# EnsembleFour.net
KiCad netlist of a schematic drawn in EAGLE
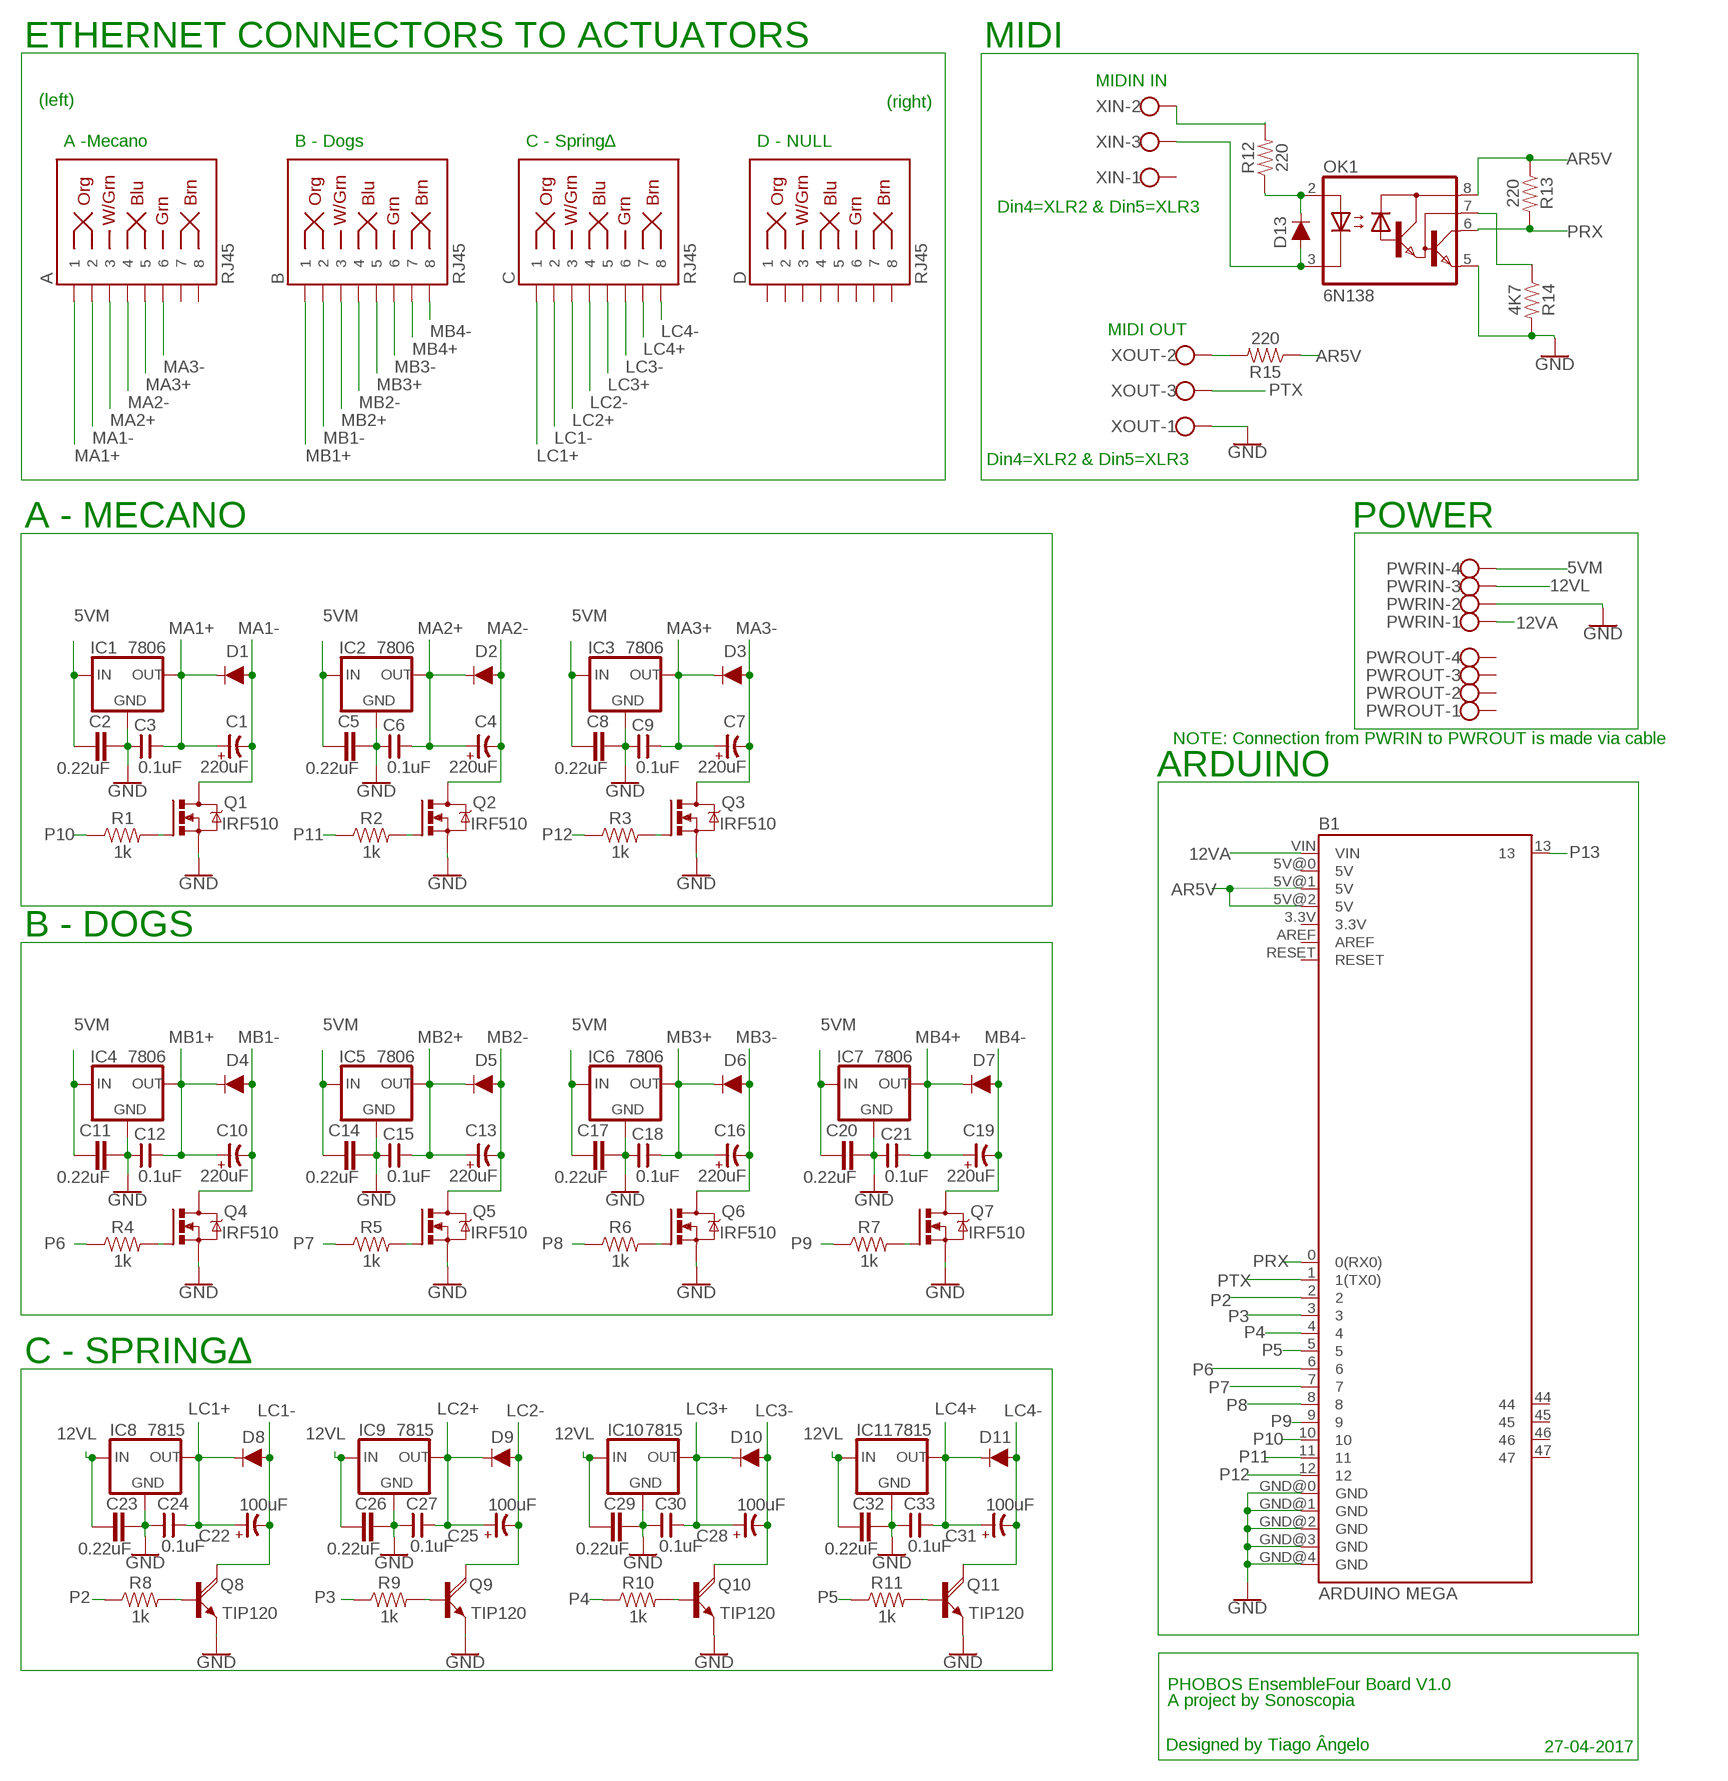
[diagram p0: schematic, sheet 1]

(export (version "E")
  (design (tool "Eeschema 10.0.6"))
  (components
    (comp (ref "A")
      (value "RJ45")
      (footprint "eagle-import:RJ45-8")
      (libsource (lib "eagle-import") (part "RJ45-8"))
    )
    (comp (ref "B")
      (value "RJ45")
      (footprint "eagle-import:RJ45-8")
      (libsource (lib "eagle-import") (part "RJ45-8"))
    )
    (comp (ref "B1")
      (value "ARDUINO MEGA")
      (footprint "eagle-import:ARDUINO_MEGA")
      (libsource (lib "eagle-import") (part "ARDUINO_MEGA_R3FULL"))
    )
    (comp (ref "C")
      (value "RJ45")
      (footprint "eagle-import:RJ45-8")
      (libsource (lib "eagle-import") (part "RJ45-8"))
    )
    (comp (ref "C1")
      (value "220uF")
      (footprint "eagle-import:E-035X080")
      (libsource (lib "eagle-import") (part "CP-E-035X080"))
    )
    (comp (ref "C2")
      (value "0.22uF")
      (footprint "eagle-import:C5B3")
      (libsource (lib "eagle-import") (part "C5/3"))
    )
    (comp (ref "C3")
      (value "0.1uF")
      (footprint "eagle-import:C025-050X025")
      (libsource (lib "eagle-import") (part "CNP-C025-050X025"))
    )
    (comp (ref "C4")
      (value "220uF")
      (footprint "eagle-import:E-035X080")
      (libsource (lib "eagle-import") (part "CP-E-035X080"))
    )
    (comp (ref "C5")
      (value "0.22uF")
      (footprint "eagle-import:C5B3")
      (libsource (lib "eagle-import") (part "C5/3"))
    )
    (comp (ref "C6")
      (value "0.1uF")
      (footprint "eagle-import:C025-050X025")
      (libsource (lib "eagle-import") (part "CNP-C025-050X025"))
    )
    (comp (ref "C7")
      (value "220uF")
      (footprint "eagle-import:E-035X080")
      (libsource (lib "eagle-import") (part "CP-E-035X080"))
    )
    (comp (ref "C8")
      (value "0.22uF")
      (footprint "eagle-import:C5B3")
      (libsource (lib "eagle-import") (part "C5/3"))
    )
    (comp (ref "C9")
      (value "0.1uF")
      (footprint "eagle-import:C025-050X025")
      (libsource (lib "eagle-import") (part "CNP-C025-050X025"))
    )
    (comp (ref "C10")
      (value "220uF")
      (footprint "eagle-import:E-035X080")
      (libsource (lib "eagle-import") (part "CP-E-035X080"))
    )
    (comp (ref "C11")
      (value "0.22uF")
      (footprint "eagle-import:C5B3")
      (libsource (lib "eagle-import") (part "C5/3"))
    )
    (comp (ref "C12")
      (value "0.1uF")
      (footprint "eagle-import:C025-050X025")
      (libsource (lib "eagle-import") (part "CNP-C025-050X025"))
    )
    (comp (ref "C13")
      (value "220uF")
      (footprint "eagle-import:E-035X080")
      (libsource (lib "eagle-import") (part "CP-E-035X080"))
    )
    (comp (ref "C14")
      (value "0.22uF")
      (footprint "eagle-import:C5B3")
      (libsource (lib "eagle-import") (part "C5/3"))
    )
    (comp (ref "C15")
      (value "0.1uF")
      (footprint "eagle-import:C025-050X025")
      (libsource (lib "eagle-import") (part "CNP-C025-050X025"))
    )
    (comp (ref "C16")
      (value "220uF")
      (footprint "eagle-import:E-035X080")
      (libsource (lib "eagle-import") (part "CP-E-035X080"))
    )
    (comp (ref "C17")
      (value "0.22uF")
      (footprint "eagle-import:C5B3")
      (libsource (lib "eagle-import") (part "C5/3"))
    )
    (comp (ref "C18")
      (value "0.1uF")
      (footprint "eagle-import:C025-050X025")
      (libsource (lib "eagle-import") (part "CNP-C025-050X025"))
    )
    (comp (ref "C19")
      (value "220uF")
      (footprint "eagle-import:E-035X080")
      (libsource (lib "eagle-import") (part "CP-E-035X080"))
    )
    (comp (ref "C20")
      (value "0.22uF")
      (footprint "eagle-import:C5B3")
      (libsource (lib "eagle-import") (part "C5/3"))
    )
    (comp (ref "C21")
      (value "0.1uF")
      (footprint "eagle-import:C025-050X025")
      (libsource (lib "eagle-import") (part "CNP-C025-050X025"))
    )
    (comp (ref "C22")
      (value "100uF")
      (footprint "eagle-import:E-020X050")
      (libsource (lib "eagle-import") (part "CP-E-020X050"))
    )
    (comp (ref "C23")
      (value "0.22uF")
      (footprint "eagle-import:C5B3")
      (libsource (lib "eagle-import") (part "C5/3"))
    )
    (comp (ref "C24")
      (value "0.1uF")
      (footprint "eagle-import:C025-050X025")
      (libsource (lib "eagle-import") (part "CNP-C025-050X025"))
    )
    (comp (ref "C25")
      (value "100uF")
      (footprint "eagle-import:E-020X050")
      (libsource (lib "eagle-import") (part "CP-E-020X050"))
    )
    (comp (ref "C26")
      (value "0.22uF")
      (footprint "eagle-import:C5B3")
      (libsource (lib "eagle-import") (part "C5/3"))
    )
    (comp (ref "C27")
      (value "0.1uF")
      (footprint "eagle-import:C025-050X025")
      (libsource (lib "eagle-import") (part "CNP-C025-050X025"))
    )
    (comp (ref "C28")
      (value "100uF")
      (footprint "eagle-import:E-020X050")
      (libsource (lib "eagle-import") (part "CP-E-020X050"))
    )
    (comp (ref "C29")
      (value "0.22uF")
      (footprint "eagle-import:C5B3")
      (libsource (lib "eagle-import") (part "C5/3"))
    )
    (comp (ref "C30")
      (value "0.1uF")
      (footprint "eagle-import:C025-050X025")
      (libsource (lib "eagle-import") (part "CNP-C025-050X025"))
    )
    (comp (ref "C31")
      (value "100uF")
      (footprint "eagle-import:E-020X050")
      (libsource (lib "eagle-import") (part "CP-E-020X050"))
    )
    (comp (ref "C32")
      (value "0.22uF")
      (footprint "eagle-import:C5B3")
      (libsource (lib "eagle-import") (part "C5/3"))
    )
    (comp (ref "C33")
      (value "0.1uF")
      (footprint "eagle-import:C025-050X025")
      (libsource (lib "eagle-import") (part "CNP-C025-050X025"))
    )
    (comp (ref "D")
      (value "RJ45")
      (footprint "eagle-import:RJ45-8")
      (libsource (lib "eagle-import") (part "RJ45-8"))
    )
    (comp (ref "D1")
      (value "1A/50V/1.1V")
      (footprint "eagle-import:DIODE-1N4001-KIT")
      (libsource (lib "eagle-import") (part "DIODE-KIT2"))
    )
    (comp (ref "D2")
      (value "1A/50V/1.1V")
      (footprint "eagle-import:DIODE-1N4001-KIT")
      (libsource (lib "eagle-import") (part "DIODE-KIT2"))
    )
    (comp (ref "D3")
      (value "1A/50V/1.1V")
      (footprint "eagle-import:DIODE-1N4001-KIT")
      (libsource (lib "eagle-import") (part "DIODE-KIT2"))
    )
    (comp (ref "D4")
      (value "1A/50V/1.1V")
      (footprint "eagle-import:DIODE-1N4001-KIT")
      (libsource (lib "eagle-import") (part "DIODE-KIT2"))
    )
    (comp (ref "D5")
      (value "1A/50V/1.1V")
      (footprint "eagle-import:DIODE-1N4001-KIT")
      (libsource (lib "eagle-import") (part "DIODE-KIT2"))
    )
    (comp (ref "D6")
      (value "1A/50V/1.1V")
      (footprint "eagle-import:DIODE-1N4001-KIT")
      (libsource (lib "eagle-import") (part "DIODE-KIT2"))
    )
    (comp (ref "D7")
      (value "1A/50V/1.1V")
      (footprint "eagle-import:DIODE-1N4001-KIT")
      (libsource (lib "eagle-import") (part "DIODE-KIT2"))
    )
    (comp (ref "D8")
      (value "1A/50V/1.1V")
      (footprint "eagle-import:DIODE-1N4001-KIT")
      (libsource (lib "eagle-import") (part "DIODE-KIT2"))
    )
    (comp (ref "D9")
      (value "1A/50V/1.1V")
      (footprint "eagle-import:DIODE-1N4001-KIT")
      (libsource (lib "eagle-import") (part "DIODE-KIT2"))
    )
    (comp (ref "D10")
      (value "1A/50V/1.1V")
      (footprint "eagle-import:DIODE-1N4001-KIT")
      (libsource (lib "eagle-import") (part "DIODE-KIT2"))
    )
    (comp (ref "D11")
      (value "1A/50V/1.1V")
      (footprint "eagle-import:DIODE-1N4001-KIT")
      (libsource (lib "eagle-import") (part "DIODE-KIT2"))
    )
    (comp (ref "D13")
      (value "200mA/100V/1V")
      (footprint "eagle-import:DIODE-1N4148")
      (libsource (lib "eagle-import") (part "DIODE-1N4148"))
    )
    (comp (ref "IC1")
      (value "7806")
      (footprint "eagle-import:78XXS")
      (libsource (lib "eagle-import") (part "78XXS"))
    )
    (comp (ref "IC2")
      (value "7806")
      (footprint "eagle-import:78XXS")
      (libsource (lib "eagle-import") (part "78XXS"))
    )
    (comp (ref "IC3")
      (value "7806")
      (footprint "eagle-import:78XXS")
      (libsource (lib "eagle-import") (part "78XXS"))
    )
    (comp (ref "IC4")
      (value "7806")
      (footprint "eagle-import:78XXS")
      (libsource (lib "eagle-import") (part "78XXS"))
    )
    (comp (ref "IC5")
      (value "7806")
      (footprint "eagle-import:78XXS")
      (libsource (lib "eagle-import") (part "78XXS"))
    )
    (comp (ref "IC6")
      (value "7806")
      (footprint "eagle-import:78XXS")
      (libsource (lib "eagle-import") (part "78XXS"))
    )
    (comp (ref "IC7")
      (value "7806")
      (footprint "eagle-import:78XXS")
      (libsource (lib "eagle-import") (part "78XXS"))
    )
    (comp (ref "IC8")
      (value "7815")
      (footprint "eagle-import:78XXS")
      (libsource (lib "eagle-import") (part "78XXS"))
    )
    (comp (ref "IC9")
      (value "7815")
      (footprint "eagle-import:78XXS")
      (libsource (lib "eagle-import") (part "78XXS"))
    )
    (comp (ref "IC10")
      (value "7815")
      (footprint "eagle-import:78XXS")
      (libsource (lib "eagle-import") (part "78XXS"))
    )
    (comp (ref "IC11")
      (value "7815")
      (footprint "eagle-import:78XXS")
      (libsource (lib "eagle-import") (part "78XXS"))
    )
    (comp (ref "OK1")
      (value "6N138")
      (footprint "eagle-import:DIL08")
      (fields (field (name "MF") "VISHAY/TELEFUNKEN"))
      (libsource (lib "eagle-import") (part "6N138"))
    )
    (comp (ref "PWRIN")
      (value "W237-4")
      (footprint "eagle-import:W237-4")
      (libsource (lib "eagle-import") (part "W237-4"))
    )
    (comp (ref "PWROUT")
      (value "W237-4")
      (footprint "eagle-import:W237-4")
      (libsource (lib "eagle-import") (part "W237-4"))
    )
    (comp (ref "Q1")
      (value "IRF510")
      (footprint "eagle-import:TO220BV")
      (libsource (lib "eagle-import") (part "IRF520"))
    )
    (comp (ref "Q2")
      (value "IRF510")
      (footprint "eagle-import:TO220BV")
      (libsource (lib "eagle-import") (part "IRF520"))
    )
    (comp (ref "Q3")
      (value "IRF510")
      (footprint "eagle-import:TO220BV")
      (libsource (lib "eagle-import") (part "IRF520"))
    )
    (comp (ref "Q4")
      (value "IRF510")
      (footprint "eagle-import:TO220BV")
      (libsource (lib "eagle-import") (part "IRF520"))
    )
    (comp (ref "Q5")
      (value "IRF510")
      (footprint "eagle-import:TO220BV")
      (libsource (lib "eagle-import") (part "IRF520"))
    )
    (comp (ref "Q6")
      (value "IRF510")
      (footprint "eagle-import:TO220BV")
      (libsource (lib "eagle-import") (part "IRF520"))
    )
    (comp (ref "Q7")
      (value "IRF510")
      (footprint "eagle-import:TO220BV")
      (libsource (lib "eagle-import") (part "IRF520"))
    )
    (comp (ref "Q8")
      (value "TIP120")
      (footprint "eagle-import:TO220AV")
      (libsource (lib "eagle-import") (part "TIP120V"))
    )
    (comp (ref "Q9")
      (value "TIP120")
      (footprint "eagle-import:TO220AV")
      (libsource (lib "eagle-import") (part "TIP120V"))
    )
    (comp (ref "Q10")
      (value "TIP120")
      (footprint "eagle-import:TO220AV")
      (libsource (lib "eagle-import") (part "TIP120V"))
    )
    (comp (ref "Q11")
      (value "TIP120")
      (footprint "eagle-import:TO220AV")
      (libsource (lib "eagle-import") (part "TIP120V"))
    )
    (comp (ref "R1")
      (value "1k")
      (footprint "eagle-import:AXIAL-0.1")
      (libsource (lib "eagle-import") (part "1KOHM-VERT-1/4W-1%"))
    )
    (comp (ref "R2")
      (value "1k")
      (footprint "eagle-import:AXIAL-0.1")
      (libsource (lib "eagle-import") (part "1KOHM-VERT-1/4W-1%"))
    )
    (comp (ref "R3")
      (value "1k")
      (footprint "eagle-import:AXIAL-0.1")
      (libsource (lib "eagle-import") (part "1KOHM-VERT-1/4W-1%"))
    )
    (comp (ref "R4")
      (value "1k")
      (footprint "eagle-import:AXIAL-0.1")
      (libsource (lib "eagle-import") (part "1KOHM-VERT-1/4W-1%"))
    )
    (comp (ref "R5")
      (value "1k")
      (footprint "eagle-import:AXIAL-0.1")
      (libsource (lib "eagle-import") (part "1KOHM-VERT-1/4W-1%"))
    )
    (comp (ref "R6")
      (value "1k")
      (footprint "eagle-import:AXIAL-0.1")
      (libsource (lib "eagle-import") (part "1KOHM-VERT-1/4W-1%"))
    )
    (comp (ref "R7")
      (value "1k")
      (footprint "eagle-import:AXIAL-0.1")
      (libsource (lib "eagle-import") (part "1KOHM-VERT-1/4W-1%"))
    )
    (comp (ref "R8")
      (value "1k")
      (footprint "eagle-import:AXIAL-0.1")
      (libsource (lib "eagle-import") (part "1KOHM-VERT-1/4W-1%"))
    )
    (comp (ref "R9")
      (value "1k")
      (footprint "eagle-import:AXIAL-0.1")
      (libsource (lib "eagle-import") (part "1KOHM-VERT-1/4W-1%"))
    )
    (comp (ref "R10")
      (value "1k")
      (footprint "eagle-import:AXIAL-0.1")
      (libsource (lib "eagle-import") (part "1KOHM-VERT-1/4W-1%"))
    )
    (comp (ref "R11")
      (value "1k")
      (footprint "eagle-import:AXIAL-0.1")
      (libsource (lib "eagle-import") (part "1KOHM-VERT-1/4W-1%"))
    )
    (comp (ref "R12")
      (value "220")
      (footprint "eagle-import:AXIAL-0.3")
      (libsource (lib "eagle-import") (part "1KOHM-HORIZ-1/4W-5%"))
    )
    (comp (ref "R13")
      (value "220")
      (footprint "eagle-import:AXIAL-0.3")
      (libsource (lib "eagle-import") (part "1KOHM-HORIZ-1/4W-5%"))
    )
    (comp (ref "R14")
      (value "4K7")
      (footprint "eagle-import:AXIAL-0.3")
      (libsource (lib "eagle-import") (part "1KOHM-HORIZ-1/4W-5%"))
    )
    (comp (ref "R15")
      (value "220")
      (footprint "eagle-import:AXIAL-0.3")
      (libsource (lib "eagle-import") (part "1KOHM-HORIZ-1/4W-5%"))
    )
    (comp (ref "XIN")
      (value "W237-103")
      (footprint "eagle-import:W237-103")
      (fields (field (name "MPN") "237-103"))
      (libsource (lib "eagle-import") (part "W237-103"))
    )
    (comp (ref "XOUT")
      (value "W237-103")
      (footprint "eagle-import:W237-103")
      (fields (field (name "MPN") "237-103"))
      (libsource (lib "eagle-import") (part "W237-103"))
    )
  )
  (nets
    (net (code "1") (name "/5VM") (class "Default")
      (node (ref "C11") (pin "1") (pinfunction "1_1") (pintype "passive"))
      (node (ref "C14") (pin "1") (pinfunction "1_1") (pintype "passive"))
      (node (ref "C17") (pin "1") (pinfunction "1_1") (pintype "passive"))
      (node (ref "C2") (pin "1") (pinfunction "1_1") (pintype "passive"))
      (node (ref "C20") (pin "1") (pinfunction "1_1") (pintype "passive"))
      (node (ref "C5") (pin "1") (pinfunction "1_1") (pintype "passive"))
      (node (ref "C8") (pin "1") (pinfunction "1_1") (pintype "passive"))
      (node (ref "IC1") (pin "IN") (pinfunction "IN_IN") (pintype "input"))
      (node (ref "IC2") (pin "IN") (pinfunction "IN_IN") (pintype "input"))
      (node (ref "IC3") (pin "IN") (pinfunction "IN_IN") (pintype "input"))
      (node (ref "IC4") (pin "IN") (pinfunction "IN_IN") (pintype "input"))
      (node (ref "IC5") (pin "IN") (pinfunction "IN_IN") (pintype "input"))
      (node (ref "IC6") (pin "IN") (pinfunction "IN_IN") (pintype "input"))
      (node (ref "IC7") (pin "IN") (pinfunction "IN_IN") (pintype "input"))
      (node (ref "PWRIN") (pin "4") (pinfunction "KL_4") (pintype "passive"))
    )
    (net (code "2") (name "/12VA") (class "Default")
      (node (ref "B1") (pin "VIN") (pinfunction "VIN_VIN") (pintype "bidirectional"))
      (node (ref "PWRIN") (pin "1") (pinfunction "KL_1") (pintype "passive"))
    )
    (net (code "3") (name "/12VL") (class "Default")
      (node (ref "C23") (pin "1") (pinfunction "1_1") (pintype "passive"))
      (node (ref "C26") (pin "1") (pinfunction "1_1") (pintype "passive"))
      (node (ref "C29") (pin "1") (pinfunction "1_1") (pintype "passive"))
      (node (ref "C32") (pin "1") (pinfunction "1_1") (pintype "passive"))
      (node (ref "IC10") (pin "IN") (pinfunction "IN_IN") (pintype "input"))
      (node (ref "IC11") (pin "IN") (pinfunction "IN_IN") (pintype "input"))
      (node (ref "IC8") (pin "IN") (pinfunction "IN_IN") (pintype "input"))
      (node (ref "IC9") (pin "IN") (pinfunction "IN_IN") (pintype "input"))
      (node (ref "PWRIN") (pin "3") (pinfunction "KL_3") (pintype "passive"))
    )
    (net (code "4") (name "/AR5V") (class "Default")
      (node (ref "B1") (pin "5V@1") (pinfunction "5V_5V@1") (pintype "bidirectional"))
      (node (ref "B1") (pin "5V@2") (pinfunction "5V_5V@2") (pintype "bidirectional"))
      (node (ref "OK1") (pin "8") (pinfunction "VCC_8") (pintype "passive"))
      (node (ref "R13") (pin "P$1") (pinfunction "1_P$1") (pintype "passive"))
      (node (ref "R15") (pin "P$1") (pinfunction "1_P$1") (pintype "passive"))
    )
    (net (code "5") (name "/LC1+") (class "Default")
      (node (ref "C") (pin "1") (pinfunction "1_1") (pintype "bidirectional"))
      (node (ref "C22") (pin "+") (pinfunction "+_+") (pintype "passive"))
      (node (ref "C24") (pin "2") (pinfunction "2_2") (pintype "passive"))
      (node (ref "D8") (pin "C") (pinfunction "C_C") (pintype "passive"))
      (node (ref "IC8") (pin "OUT") (pinfunction "OUT_OUT") (pintype "passive"))
    )
    (net (code "6") (name "/LC1-") (class "Default")
      (node (ref "C") (pin "2") (pinfunction "2_2") (pintype "bidirectional"))
      (node (ref "C22") (pin "-") (pinfunction "-_-") (pintype "passive"))
      (node (ref "D8") (pin "A") (pinfunction "A_A") (pintype "passive"))
      (node (ref "Q8") (pin "C") (pinfunction "C_C") (pintype "passive"))
    )
    (net (code "7") (name "/LC2+") (class "Default")
      (node (ref "C") (pin "3") (pinfunction "3_3") (pintype "bidirectional"))
      (node (ref "C25") (pin "+") (pinfunction "+_+") (pintype "passive"))
      (node (ref "C27") (pin "2") (pinfunction "2_2") (pintype "passive"))
      (node (ref "D9") (pin "C") (pinfunction "C_C") (pintype "passive"))
      (node (ref "IC9") (pin "OUT") (pinfunction "OUT_OUT") (pintype "passive"))
    )
    (net (code "8") (name "/LC2-") (class "Default")
      (node (ref "C") (pin "4") (pinfunction "4_4") (pintype "bidirectional"))
      (node (ref "C25") (pin "-") (pinfunction "-_-") (pintype "passive"))
      (node (ref "D9") (pin "A") (pinfunction "A_A") (pintype "passive"))
      (node (ref "Q9") (pin "C") (pinfunction "C_C") (pintype "passive"))
    )
    (net (code "9") (name "/LC3+") (class "Default")
      (node (ref "C") (pin "5") (pinfunction "5_5") (pintype "bidirectional"))
      (node (ref "C28") (pin "+") (pinfunction "+_+") (pintype "passive"))
      (node (ref "C30") (pin "2") (pinfunction "2_2") (pintype "passive"))
      (node (ref "D10") (pin "C") (pinfunction "C_C") (pintype "passive"))
      (node (ref "IC10") (pin "OUT") (pinfunction "OUT_OUT") (pintype "passive"))
    )
    (net (code "10") (name "/LC3-") (class "Default")
      (node (ref "C") (pin "6") (pinfunction "6_6") (pintype "bidirectional"))
      (node (ref "C28") (pin "-") (pinfunction "-_-") (pintype "passive"))
      (node (ref "D10") (pin "A") (pinfunction "A_A") (pintype "passive"))
      (node (ref "Q10") (pin "C") (pinfunction "C_C") (pintype "passive"))
    )
    (net (code "11") (name "/LC4+") (class "Default")
      (node (ref "C") (pin "7") (pinfunction "7_7") (pintype "bidirectional"))
      (node (ref "C31") (pin "+") (pinfunction "+_+") (pintype "passive"))
      (node (ref "C33") (pin "2") (pinfunction "2_2") (pintype "passive"))
      (node (ref "D11") (pin "C") (pinfunction "C_C") (pintype "passive"))
      (node (ref "IC11") (pin "OUT") (pinfunction "OUT_OUT") (pintype "passive"))
    )
    (net (code "12") (name "/LC4-") (class "Default")
      (node (ref "C") (pin "8") (pinfunction "8_8") (pintype "bidirectional"))
      (node (ref "C31") (pin "-") (pinfunction "-_-") (pintype "passive"))
      (node (ref "D11") (pin "A") (pinfunction "A_A") (pintype "passive"))
      (node (ref "Q11") (pin "C") (pinfunction "C_C") (pintype "passive"))
    )
    (net (code "13") (name "/MA1+") (class "Default")
      (node (ref "A") (pin "1") (pinfunction "1_1") (pintype "bidirectional"))
      (node (ref "C1") (pin "+") (pinfunction "+_+") (pintype "passive"))
      (node (ref "C3") (pin "2") (pinfunction "2_2") (pintype "passive"))
      (node (ref "D1") (pin "C") (pinfunction "C_C") (pintype "passive"))
      (node (ref "IC1") (pin "OUT") (pinfunction "OUT_OUT") (pintype "passive"))
    )
    (net (code "14") (name "/MA1-") (class "Default")
      (node (ref "A") (pin "2") (pinfunction "2_2") (pintype "bidirectional"))
      (node (ref "C1") (pin "-") (pinfunction "-_-") (pintype "passive"))
      (node (ref "D1") (pin "A") (pinfunction "A_A") (pintype "passive"))
      (node (ref "Q1") (pin "D") (pinfunction "D_D") (pintype "passive"))
    )
    (net (code "15") (name "/MA2+") (class "Default")
      (node (ref "A") (pin "3") (pinfunction "3_3") (pintype "bidirectional"))
      (node (ref "C4") (pin "+") (pinfunction "+_+") (pintype "passive"))
      (node (ref "C6") (pin "2") (pinfunction "2_2") (pintype "passive"))
      (node (ref "D2") (pin "C") (pinfunction "C_C") (pintype "passive"))
      (node (ref "IC2") (pin "OUT") (pinfunction "OUT_OUT") (pintype "passive"))
    )
    (net (code "16") (name "/MA2-") (class "Default")
      (node (ref "A") (pin "4") (pinfunction "4_4") (pintype "bidirectional"))
      (node (ref "C4") (pin "-") (pinfunction "-_-") (pintype "passive"))
      (node (ref "D2") (pin "A") (pinfunction "A_A") (pintype "passive"))
      (node (ref "Q2") (pin "D") (pinfunction "D_D") (pintype "passive"))
    )
    (net (code "17") (name "/MA3+") (class "Default")
      (node (ref "A") (pin "5") (pinfunction "5_5") (pintype "bidirectional"))
      (node (ref "C7") (pin "+") (pinfunction "+_+") (pintype "passive"))
      (node (ref "C9") (pin "2") (pinfunction "2_2") (pintype "passive"))
      (node (ref "D3") (pin "C") (pinfunction "C_C") (pintype "passive"))
      (node (ref "IC3") (pin "OUT") (pinfunction "OUT_OUT") (pintype "passive"))
    )
    (net (code "18") (name "/MA3-") (class "Default")
      (node (ref "A") (pin "6") (pinfunction "6_6") (pintype "bidirectional"))
      (node (ref "C7") (pin "-") (pinfunction "-_-") (pintype "passive"))
      (node (ref "D3") (pin "A") (pinfunction "A_A") (pintype "passive"))
      (node (ref "Q3") (pin "D") (pinfunction "D_D") (pintype "passive"))
    )
    (net (code "19") (name "/MB1+") (class "Default")
      (node (ref "B") (pin "1") (pinfunction "1_1") (pintype "bidirectional"))
      (node (ref "C10") (pin "+") (pinfunction "+_+") (pintype "passive"))
      (node (ref "C12") (pin "2") (pinfunction "2_2") (pintype "passive"))
      (node (ref "D4") (pin "C") (pinfunction "C_C") (pintype "passive"))
      (node (ref "IC4") (pin "OUT") (pinfunction "OUT_OUT") (pintype "passive"))
    )
    (net (code "20") (name "/MB1-") (class "Default")
      (node (ref "B") (pin "2") (pinfunction "2_2") (pintype "bidirectional"))
      (node (ref "C10") (pin "-") (pinfunction "-_-") (pintype "passive"))
      (node (ref "D4") (pin "A") (pinfunction "A_A") (pintype "passive"))
      (node (ref "Q4") (pin "D") (pinfunction "D_D") (pintype "passive"))
    )
    (net (code "21") (name "/MB2+") (class "Default")
      (node (ref "B") (pin "3") (pinfunction "3_3") (pintype "bidirectional"))
      (node (ref "C13") (pin "+") (pinfunction "+_+") (pintype "passive"))
      (node (ref "C15") (pin "2") (pinfunction "2_2") (pintype "passive"))
      (node (ref "D5") (pin "C") (pinfunction "C_C") (pintype "passive"))
      (node (ref "IC5") (pin "OUT") (pinfunction "OUT_OUT") (pintype "passive"))
    )
    (net (code "22") (name "/MB2-") (class "Default")
      (node (ref "B") (pin "4") (pinfunction "4_4") (pintype "bidirectional"))
      (node (ref "C13") (pin "-") (pinfunction "-_-") (pintype "passive"))
      (node (ref "D5") (pin "A") (pinfunction "A_A") (pintype "passive"))
      (node (ref "Q5") (pin "D") (pinfunction "D_D") (pintype "passive"))
    )
    (net (code "23") (name "/MB3+") (class "Default")
      (node (ref "B") (pin "5") (pinfunction "5_5") (pintype "bidirectional"))
      (node (ref "C16") (pin "+") (pinfunction "+_+") (pintype "passive"))
      (node (ref "C18") (pin "2") (pinfunction "2_2") (pintype "passive"))
      (node (ref "D6") (pin "C") (pinfunction "C_C") (pintype "passive"))
      (node (ref "IC6") (pin "OUT") (pinfunction "OUT_OUT") (pintype "passive"))
    )
    (net (code "24") (name "/MB3-") (class "Default")
      (node (ref "B") (pin "6") (pinfunction "6_6") (pintype "bidirectional"))
      (node (ref "C16") (pin "-") (pinfunction "-_-") (pintype "passive"))
      (node (ref "D6") (pin "A") (pinfunction "A_A") (pintype "passive"))
      (node (ref "Q6") (pin "D") (pinfunction "D_D") (pintype "passive"))
    )
    (net (code "25") (name "/MB4+") (class "Default")
      (node (ref "B") (pin "7") (pinfunction "7_7") (pintype "bidirectional"))
      (node (ref "C19") (pin "+") (pinfunction "+_+") (pintype "passive"))
      (node (ref "C21") (pin "2") (pinfunction "2_2") (pintype "passive"))
      (node (ref "D7") (pin "C") (pinfunction "C_C") (pintype "passive"))
      (node (ref "IC7") (pin "OUT") (pinfunction "OUT_OUT") (pintype "passive"))
    )
    (net (code "26") (name "/MB4-") (class "Default")
      (node (ref "B") (pin "8") (pinfunction "8_8") (pintype "bidirectional"))
      (node (ref "C19") (pin "-") (pinfunction "-_-") (pintype "passive"))
      (node (ref "D7") (pin "A") (pinfunction "A_A") (pintype "passive"))
      (node (ref "Q7") (pin "D") (pinfunction "D_D") (pintype "passive"))
    )
    (net (code "27") (name "/P2") (class "Default")
      (node (ref "B1") (pin "2") (pinfunction "2_2") (pintype "bidirectional"))
      (node (ref "R8") (pin "P$1") (pinfunction "1_P$1") (pintype "passive"))
    )
    (net (code "28") (name "/P3") (class "Default")
      (node (ref "B1") (pin "3") (pinfunction "3_3") (pintype "bidirectional"))
      (node (ref "R9") (pin "P$1") (pinfunction "1_P$1") (pintype "passive"))
    )
    (net (code "29") (name "/P4") (class "Default")
      (node (ref "B1") (pin "4") (pinfunction "4_4") (pintype "bidirectional"))
      (node (ref "R10") (pin "P$1") (pinfunction "1_P$1") (pintype "passive"))
    )
    (net (code "30") (name "/P5") (class "Default")
      (node (ref "B1") (pin "5") (pinfunction "5_5") (pintype "bidirectional"))
      (node (ref "R11") (pin "P$1") (pinfunction "1_P$1") (pintype "passive"))
    )
    (net (code "31") (name "/P6") (class "Default")
      (node (ref "B1") (pin "6") (pinfunction "6_6") (pintype "bidirectional"))
      (node (ref "R4") (pin "P$1") (pinfunction "1_P$1") (pintype "passive"))
    )
    (net (code "32") (name "/P7") (class "Default")
      (node (ref "B1") (pin "7") (pinfunction "7_7") (pintype "bidirectional"))
      (node (ref "R5") (pin "P$1") (pinfunction "1_P$1") (pintype "passive"))
    )
    (net (code "33") (name "/P8") (class "Default")
      (node (ref "B1") (pin "8") (pinfunction "8_8") (pintype "bidirectional"))
      (node (ref "R6") (pin "P$1") (pinfunction "1_P$1") (pintype "passive"))
    )
    (net (code "34") (name "/P9") (class "Default")
      (node (ref "B1") (pin "9") (pinfunction "9_9") (pintype "bidirectional"))
      (node (ref "R7") (pin "P$1") (pinfunction "1_P$1") (pintype "passive"))
    )
    (net (code "35") (name "/P10") (class "Default")
      (node (ref "B1") (pin "10") (pinfunction "10_10") (pintype "bidirectional"))
      (node (ref "R1") (pin "P$1") (pinfunction "1_P$1") (pintype "passive"))
    )
    (net (code "36") (name "/P11") (class "Default")
      (node (ref "B1") (pin "11") (pinfunction "11_11") (pintype "bidirectional"))
      (node (ref "R2") (pin "P$1") (pinfunction "1_P$1") (pintype "passive"))
    )
    (net (code "37") (name "/P12") (class "Default")
      (node (ref "B1") (pin "12") (pinfunction "12_12") (pintype "bidirectional"))
      (node (ref "R3") (pin "P$1") (pinfunction "1_P$1") (pintype "passive"))
    )
    (net (code "38") (name "/P13") (class "Default")
      (node (ref "B1") (pin "13") (pinfunction "13_13") (pintype "bidirectional"))
    )
    (net (code "39") (name "/PRX") (class "Default")
      (node (ref "B1") (pin "0") (pinfunction "0(RX0)_0") (pintype "bidirectional"))
      (node (ref "OK1") (pin "6") (pinfunction "VO_6") (pintype "passive"))
      (node (ref "R13") (pin "P$2") (pinfunction "2_P$2") (pintype "passive"))
    )
    (net (code "40") (name "/PTX") (class "Default")
      (node (ref "B1") (pin "1") (pinfunction "1(TX0)_1") (pintype "bidirectional"))
      (node (ref "XOUT") (pin "3") (pinfunction "KL_3") (pintype "passive"))
    )
    (net (code "41") (name "GND") (class "Default")
      (node (ref "B1") (pin "GND@0") (pinfunction "GND_GND@0") (pintype "bidirectional"))
      (node (ref "B1") (pin "GND@1") (pinfunction "GND_GND@1") (pintype "bidirectional"))
      (node (ref "B1") (pin "GND@2") (pinfunction "GND_GND@2") (pintype "bidirectional"))
      (node (ref "B1") (pin "GND@3") (pinfunction "GND_GND@3") (pintype "bidirectional"))
      (node (ref "B1") (pin "GND@4") (pinfunction "GND_GND@4") (pintype "bidirectional"))
      (node (ref "C11") (pin "2") (pinfunction "2_2") (pintype "passive"))
      (node (ref "C12") (pin "1") (pinfunction "1_1") (pintype "passive"))
      (node (ref "C14") (pin "2") (pinfunction "2_2") (pintype "passive"))
      (node (ref "C15") (pin "1") (pinfunction "1_1") (pintype "passive"))
      (node (ref "C17") (pin "2") (pinfunction "2_2") (pintype "passive"))
      (node (ref "C18") (pin "1") (pinfunction "1_1") (pintype "passive"))
      (node (ref "C2") (pin "2") (pinfunction "2_2") (pintype "passive"))
      (node (ref "C20") (pin "2") (pinfunction "2_2") (pintype "passive"))
      (node (ref "C21") (pin "1") (pinfunction "1_1") (pintype "passive"))
      (node (ref "C23") (pin "2") (pinfunction "2_2") (pintype "passive"))
      (node (ref "C24") (pin "1") (pinfunction "1_1") (pintype "passive"))
      (node (ref "C26") (pin "2") (pinfunction "2_2") (pintype "passive"))
      (node (ref "C27") (pin "1") (pinfunction "1_1") (pintype "passive"))
      (node (ref "C29") (pin "2") (pinfunction "2_2") (pintype "passive"))
      (node (ref "C3") (pin "1") (pinfunction "1_1") (pintype "passive"))
      (node (ref "C30") (pin "1") (pinfunction "1_1") (pintype "passive"))
      (node (ref "C32") (pin "2") (pinfunction "2_2") (pintype "passive"))
      (node (ref "C33") (pin "1") (pinfunction "1_1") (pintype "passive"))
      (node (ref "C5") (pin "2") (pinfunction "2_2") (pintype "passive"))
      (node (ref "C6") (pin "1") (pinfunction "1_1") (pintype "passive"))
      (node (ref "C8") (pin "2") (pinfunction "2_2") (pintype "passive"))
      (node (ref "C9") (pin "1") (pinfunction "1_1") (pintype "passive"))
      (node (ref "IC1") (pin "GND") (pinfunction "GND_GND") (pintype "input"))
      (node (ref "IC10") (pin "GND") (pinfunction "GND_GND") (pintype "input"))
      (node (ref "IC11") (pin "GND") (pinfunction "GND_GND") (pintype "input"))
      (node (ref "IC2") (pin "GND") (pinfunction "GND_GND") (pintype "input"))
      (node (ref "IC3") (pin "GND") (pinfunction "GND_GND") (pintype "input"))
      (node (ref "IC4") (pin "GND") (pinfunction "GND_GND") (pintype "input"))
      (node (ref "IC5") (pin "GND") (pinfunction "GND_GND") (pintype "input"))
      (node (ref "IC6") (pin "GND") (pinfunction "GND_GND") (pintype "input"))
      (node (ref "IC7") (pin "GND") (pinfunction "GND_GND") (pintype "input"))
      (node (ref "IC8") (pin "GND") (pinfunction "GND_GND") (pintype "input"))
      (node (ref "IC9") (pin "GND") (pinfunction "GND_GND") (pintype "input"))
      (node (ref "OK1") (pin "5") (pinfunction "GND_5") (pintype "passive"))
      (node (ref "PWRIN") (pin "2") (pinfunction "KL_2") (pintype "passive"))
      (node (ref "Q1") (pin "S") (pinfunction "S_S") (pintype "passive"))
      (node (ref "Q10") (pin "E") (pinfunction "E_E") (pintype "passive"))
      (node (ref "Q11") (pin "E") (pinfunction "E_E") (pintype "passive"))
      (node (ref "Q2") (pin "S") (pinfunction "S_S") (pintype "passive"))
      (node (ref "Q3") (pin "S") (pinfunction "S_S") (pintype "passive"))
      (node (ref "Q4") (pin "S") (pinfunction "S_S") (pintype "passive"))
      (node (ref "Q5") (pin "S") (pinfunction "S_S") (pintype "passive"))
      (node (ref "Q6") (pin "S") (pinfunction "S_S") (pintype "passive"))
      (node (ref "Q7") (pin "S") (pinfunction "S_S") (pintype "passive"))
      (node (ref "Q8") (pin "E") (pinfunction "E_E") (pintype "passive"))
      (node (ref "Q9") (pin "E") (pinfunction "E_E") (pintype "passive"))
      (node (ref "R14") (pin "P$2") (pinfunction "2_P$2") (pintype "passive"))
      (node (ref "XOUT") (pin "1") (pinfunction "KL_1") (pintype "passive"))
    )
    (net (code "42") (name "Net-(OK1-A)") (class "Default")
      (node (ref "D13") (pin "C") (pinfunction "C_C") (pintype "passive"))
      (node (ref "OK1") (pin "2") (pinfunction "A_2") (pintype "passive"))
      (node (ref "R12") (pin "P$1") (pinfunction "1_P$1") (pintype "passive"))
    )
    (net (code "43") (name "Net-(OK1-C)") (class "Default")
      (node (ref "D13") (pin "A") (pinfunction "A_A") (pintype "passive"))
      (node (ref "OK1") (pin "3") (pinfunction "C_3") (pintype "passive"))
      (node (ref "XIN") (pin "3") (pinfunction "KL_3") (pintype "passive"))
    )
    (net (code "44") (name "Net-(OK1-VB)") (class "Default")
      (node (ref "OK1") (pin "7") (pinfunction "VB_7") (pintype "passive"))
      (node (ref "R14") (pin "P$1") (pinfunction "1_P$1") (pintype "passive"))
    )
    (net (code "45") (name "Net-(R1-2)") (class "Default")
      (node (ref "Q1") (pin "G") (pinfunction "G_G") (pintype "passive"))
      (node (ref "R1") (pin "P$2") (pinfunction "2_P$2") (pintype "passive"))
    )
    (net (code "46") (name "Net-(R2-2)") (class "Default")
      (node (ref "Q2") (pin "G") (pinfunction "G_G") (pintype "passive"))
      (node (ref "R2") (pin "P$2") (pinfunction "2_P$2") (pintype "passive"))
    )
    (net (code "47") (name "Net-(R3-2)") (class "Default")
      (node (ref "Q3") (pin "G") (pinfunction "G_G") (pintype "passive"))
      (node (ref "R3") (pin "P$2") (pinfunction "2_P$2") (pintype "passive"))
    )
    (net (code "48") (name "Net-(R4-2)") (class "Default")
      (node (ref "Q4") (pin "G") (pinfunction "G_G") (pintype "passive"))
      (node (ref "R4") (pin "P$2") (pinfunction "2_P$2") (pintype "passive"))
    )
    (net (code "49") (name "Net-(R5-2)") (class "Default")
      (node (ref "Q5") (pin "G") (pinfunction "G_G") (pintype "passive"))
      (node (ref "R5") (pin "P$2") (pinfunction "2_P$2") (pintype "passive"))
    )
    (net (code "50") (name "Net-(R6-2)") (class "Default")
      (node (ref "Q6") (pin "G") (pinfunction "G_G") (pintype "passive"))
      (node (ref "R6") (pin "P$2") (pinfunction "2_P$2") (pintype "passive"))
    )
    (net (code "51") (name "Net-(R7-2)") (class "Default")
      (node (ref "Q7") (pin "G") (pinfunction "G_G") (pintype "passive"))
      (node (ref "R7") (pin "P$2") (pinfunction "2_P$2") (pintype "passive"))
    )
    (net (code "52") (name "Net-(R8-2)") (class "Default")
      (node (ref "Q8") (pin "B") (pinfunction "B_B") (pintype "passive"))
      (node (ref "R8") (pin "P$2") (pinfunction "2_P$2") (pintype "passive"))
    )
    (net (code "53") (name "Net-(R9-2)") (class "Default")
      (node (ref "Q9") (pin "B") (pinfunction "B_B") (pintype "passive"))
      (node (ref "R9") (pin "P$2") (pinfunction "2_P$2") (pintype "passive"))
    )
    (net (code "54") (name "Net-(R10-2)") (class "Default")
      (node (ref "Q10") (pin "B") (pinfunction "B_B") (pintype "passive"))
      (node (ref "R10") (pin "P$2") (pinfunction "2_P$2") (pintype "passive"))
    )
    (net (code "55") (name "Net-(R11-2)") (class "Default")
      (node (ref "Q11") (pin "B") (pinfunction "B_B") (pintype "passive"))
      (node (ref "R11") (pin "P$2") (pinfunction "2_P$2") (pintype "passive"))
    )
    (net (code "56") (name "Net-(R12-2)") (class "Default")
      (node (ref "R12") (pin "P$2") (pinfunction "2_P$2") (pintype "passive"))
      (node (ref "XIN") (pin "2") (pinfunction "KL_2") (pintype "passive"))
    )
    (net (code "57") (name "Net-(R15-2)") (class "Default")
      (node (ref "R15") (pin "P$2") (pinfunction "2_P$2") (pintype "passive"))
      (node (ref "XOUT") (pin "2") (pinfunction "KL_2") (pintype "passive"))
    )
    (net (code "58") (name "unconnected-(A-Pad7)") (class "Default")
      (node (ref "A") (pin "7") (pinfunction "7_7") (pintype "bidirectional"))
    )
    (net (code "59") (name "unconnected-(A-Pad8)") (class "Default")
      (node (ref "A") (pin "8") (pinfunction "8_8") (pintype "bidirectional"))
    )
    (net (code "60") (name "unconnected-(B1-5V-Pad5V@0)") (class "Default")
      (node (ref "B1") (pin "5V@0") (pinfunction "5V_5V@0") (pintype "bidirectional"))
    )
    (net (code "61") (name "unconnected-(B1-Pad3.3V)") (class "Default")
      (node (ref "B1") (pin "3.3V") (pinfunction "3.3V_3.3V") (pintype "bidirectional"))
    )
    (net (code "62") (name "unconnected-(B1-Pad44)") (class "Default")
      (node (ref "B1") (pin "44") (pinfunction "44_44") (pintype "bidirectional"))
    )
    (net (code "63") (name "unconnected-(B1-Pad45)") (class "Default")
      (node (ref "B1") (pin "45") (pinfunction "45_45") (pintype "bidirectional"))
    )
    (net (code "64") (name "unconnected-(B1-Pad46)") (class "Default")
      (node (ref "B1") (pin "46") (pinfunction "46_46") (pintype "bidirectional"))
    )
    (net (code "65") (name "unconnected-(B1-Pad47)") (class "Default")
      (node (ref "B1") (pin "47") (pinfunction "47_47") (pintype "bidirectional"))
    )
    (net (code "66") (name "unconnected-(B1-PadAREF)") (class "Default")
      (node (ref "B1") (pin "AREF") (pinfunction "AREF_AREF") (pintype "bidirectional"))
    )
    (net (code "67") (name "unconnected-(B1-PadRESET)") (class "Default")
      (node (ref "B1") (pin "RESET") (pinfunction "RESET_RESET") (pintype "bidirectional"))
    )
    (net (code "68") (name "unconnected-(D-Pad1)") (class "Default")
      (node (ref "D") (pin "1") (pinfunction "1_1") (pintype "bidirectional"))
    )
    (net (code "69") (name "unconnected-(D-Pad2)") (class "Default")
      (node (ref "D") (pin "2") (pinfunction "2_2") (pintype "bidirectional"))
    )
    (net (code "70") (name "unconnected-(D-Pad3)") (class "Default")
      (node (ref "D") (pin "3") (pinfunction "3_3") (pintype "bidirectional"))
    )
    (net (code "71") (name "unconnected-(D-Pad4)") (class "Default")
      (node (ref "D") (pin "4") (pinfunction "4_4") (pintype "bidirectional"))
    )
    (net (code "72") (name "unconnected-(D-Pad5)") (class "Default")
      (node (ref "D") (pin "5") (pinfunction "5_5") (pintype "bidirectional"))
    )
    (net (code "73") (name "unconnected-(D-Pad6)") (class "Default")
      (node (ref "D") (pin "6") (pinfunction "6_6") (pintype "bidirectional"))
    )
    (net (code "74") (name "unconnected-(D-Pad7)") (class "Default")
      (node (ref "D") (pin "7") (pinfunction "7_7") (pintype "bidirectional"))
    )
    (net (code "75") (name "unconnected-(D-Pad8)") (class "Default")
      (node (ref "D") (pin "8") (pinfunction "8_8") (pintype "bidirectional"))
    )
    (net (code "76") (name "unconnected-(PWROUTA-KL-Pad1)") (class "Default")
      (node (ref "PWROUT") (pin "1") (pinfunction "KL_1") (pintype "passive"))
    )
    (net (code "77") (name "unconnected-(PWROUTB-KL-Pad2)") (class "Default")
      (node (ref "PWROUT") (pin "2") (pinfunction "KL_2") (pintype "passive"))
    )
    (net (code "78") (name "unconnected-(PWROUTC-KL-Pad3)") (class "Default")
      (node (ref "PWROUT") (pin "3") (pinfunction "KL_3") (pintype "passive"))
    )
    (net (code "79") (name "unconnected-(PWROUTD-KL-Pad4)") (class "Default")
      (node (ref "PWROUT") (pin "4") (pinfunction "KL_4") (pintype "passive"))
    )
    (net (code "80") (name "unconnected-(XINA-KL-Pad1)") (class "Default")
      (node (ref "XIN") (pin "1") (pinfunction "KL_1") (pintype "passive"))
    )
  )
)
